# IDC_EXT_Connectors.net
KiCad netlist of a schematic drawn in Altium Designer
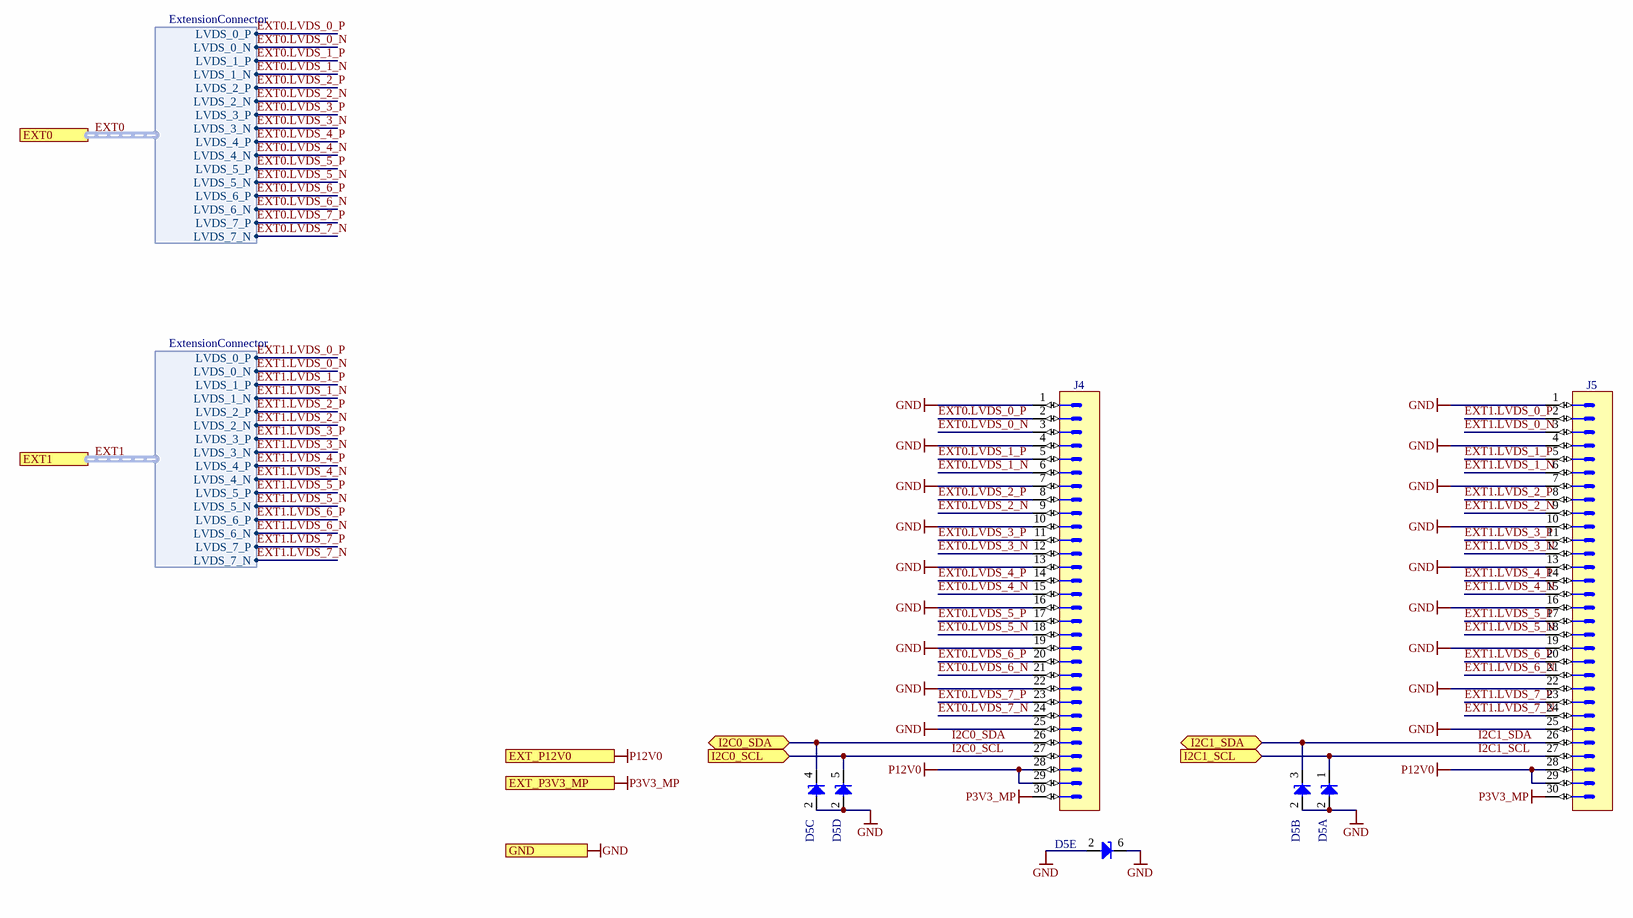
[diagram p0: IDC_EXT_Connectors.SchDoc]

(export (version "E")
  (design (tool "Eeschema 10.0.6"))
  (components
    (comp (ref "D5")
      (value "PESD3V3L5UY")
      (footprint "SOT65P210X110-6N")
      (description "Fivefold ESD Protection Diode Arrays")
      (fields
        (field (name "VOLTAGE") "3.3V")
        (field (name "POWER") "200W")
        (field (name "AUTHOR") "CERN DEM WB")
      )
      (libsource (lib "ICs And Semiconductors") (part "PESD Array 5diodes 6pins Common anode2"))
    )
    (comp (ref "J4")
      (value "~")
      (footprint "3M_N2530-6002RB")
      (description "Connector 30 Male")
      (fields
        (field (name "PART NUMBER") "3M_N2530-6002RB")
        (field (name "MANUFACTURER") "3M")
        (field (name "AUTHOR") "CERN DEM JLC")
      )
      (libsource (lib "Connectors") (part "Connector 30 Male"))
    )
    (comp (ref "J5")
      (value "~")
      (footprint "3M_N2530-6002RB")
      (description "Connector 30 Male")
      (fields
        (field (name "PART NUMBER") "3M_N2530-6002RB")
        (field (name "MANUFACTURER") "3M")
        (field (name "AUTHOR") "CERN DEM JLC")
      )
      (libsource (lib "Connectors") (part "Connector 30 Male"))
    )
  )
  (nets
    (net (code "3") (name "/EXT0.LVDS_0_N") (class "Default")
      (node (ref "J4") (pin "3") (pinfunction "3_3") (pintype "bidirectional"))
    )
    (net (code "4") (name "/EXT0.LVDS_0_P") (class "Default")
      (node (ref "J4") (pin "2") (pinfunction "2_2") (pintype "bidirectional"))
    )
    (net (code "5") (name "/EXT0.LVDS_1_N") (class "Default")
      (node (ref "J4") (pin "6") (pinfunction "6_6") (pintype "bidirectional"))
    )
    (net (code "6") (name "/EXT0.LVDS_1_P") (class "Default")
      (node (ref "J4") (pin "5") (pinfunction "5_5") (pintype "bidirectional"))
    )
    (net (code "7") (name "/EXT0.LVDS_2_N") (class "Default")
      (node (ref "J4") (pin "9") (pinfunction "9_9") (pintype "bidirectional"))
    )
    (net (code "8") (name "/EXT0.LVDS_2_P") (class "Default")
      (node (ref "J4") (pin "8") (pinfunction "8_8") (pintype "bidirectional"))
    )
    (net (code "9") (name "/EXT0.LVDS_3_N") (class "Default")
      (node (ref "J4") (pin "12") (pinfunction "12_12") (pintype "bidirectional"))
    )
    (net (code "10") (name "/EXT0.LVDS_3_P") (class "Default")
      (node (ref "J4") (pin "11") (pinfunction "11_11") (pintype "bidirectional"))
    )
    (net (code "11") (name "/EXT0.LVDS_4_N") (class "Default")
      (node (ref "J4") (pin "15") (pinfunction "15_15") (pintype "bidirectional"))
    )
    (net (code "12") (name "/EXT0.LVDS_4_P") (class "Default")
      (node (ref "J4") (pin "14") (pinfunction "14_14") (pintype "bidirectional"))
    )
    (net (code "13") (name "/EXT0.LVDS_5_N") (class "Default")
      (node (ref "J4") (pin "18") (pinfunction "18_18") (pintype "bidirectional"))
    )
    (net (code "14") (name "/EXT0.LVDS_5_P") (class "Default")
      (node (ref "J4") (pin "17") (pinfunction "17_17") (pintype "bidirectional"))
    )
    (net (code "15") (name "/EXT0.LVDS_6_N") (class "Default")
      (node (ref "J4") (pin "21") (pinfunction "21_21") (pintype "bidirectional"))
    )
    (net (code "16") (name "/EXT0.LVDS_6_P") (class "Default")
      (node (ref "J4") (pin "20") (pinfunction "20_20") (pintype "bidirectional"))
    )
    (net (code "17") (name "/EXT0.LVDS_7_N") (class "Default")
      (node (ref "J4") (pin "24") (pinfunction "24_24") (pintype "bidirectional"))
    )
    (net (code "18") (name "/EXT0.LVDS_7_P") (class "Default")
      (node (ref "J4") (pin "23") (pinfunction "23_23") (pintype "bidirectional"))
    )
    (net (code "20") (name "/EXT1.LVDS_0_N") (class "Default")
      (node (ref "J5") (pin "3") (pinfunction "3_3") (pintype "bidirectional"))
    )
    (net (code "21") (name "/EXT1.LVDS_0_P") (class "Default")
      (node (ref "J5") (pin "2") (pinfunction "2_2") (pintype "bidirectional"))
    )
    (net (code "22") (name "/EXT1.LVDS_1_N") (class "Default")
      (node (ref "J5") (pin "6") (pinfunction "6_6") (pintype "bidirectional"))
    )
    (net (code "23") (name "/EXT1.LVDS_1_P") (class "Default")
      (node (ref "J5") (pin "5") (pinfunction "5_5") (pintype "bidirectional"))
    )
    (net (code "24") (name "/EXT1.LVDS_2_N") (class "Default")
      (node (ref "J5") (pin "9") (pinfunction "9_9") (pintype "bidirectional"))
    )
    (net (code "25") (name "/EXT1.LVDS_2_P") (class "Default")
      (node (ref "J5") (pin "8") (pinfunction "8_8") (pintype "bidirectional"))
    )
    (net (code "26") (name "/EXT1.LVDS_3_N") (class "Default")
      (node (ref "J5") (pin "12") (pinfunction "12_12") (pintype "bidirectional"))
    )
    (net (code "27") (name "/EXT1.LVDS_3_P") (class "Default")
      (node (ref "J5") (pin "11") (pinfunction "11_11") (pintype "bidirectional"))
    )
    (net (code "28") (name "/EXT1.LVDS_4_N") (class "Default")
      (node (ref "J5") (pin "15") (pinfunction "15_15") (pintype "bidirectional"))
    )
    (net (code "29") (name "/EXT1.LVDS_4_P") (class "Default")
      (node (ref "J5") (pin "14") (pinfunction "14_14") (pintype "bidirectional"))
    )
    (net (code "30") (name "/EXT1.LVDS_5_N") (class "Default")
      (node (ref "J5") (pin "18") (pinfunction "18_18") (pintype "bidirectional"))
    )
    (net (code "31") (name "/EXT1.LVDS_5_P") (class "Default")
      (node (ref "J5") (pin "17") (pinfunction "17_17") (pintype "bidirectional"))
    )
    (net (code "32") (name "/EXT1.LVDS_6_N") (class "Default")
      (node (ref "J5") (pin "21") (pinfunction "21_21") (pintype "bidirectional"))
    )
    (net (code "33") (name "/EXT1.LVDS_6_P") (class "Default")
      (node (ref "J5") (pin "20") (pinfunction "20_20") (pintype "bidirectional"))
    )
    (net (code "34") (name "/EXT1.LVDS_7_N") (class "Default")
      (node (ref "J5") (pin "24") (pinfunction "24_24") (pintype "bidirectional"))
    )
    (net (code "35") (name "/EXT1.LVDS_7_P") (class "Default")
      (node (ref "J5") (pin "23") (pinfunction "23_23") (pintype "bidirectional"))
    )
    (net (code "37") (name "/I2C0_SCL") (class "Default")
      (node (ref "D5") (pin "5") (pinfunction "C_5") (pintype "passive"))
      (node (ref "J4") (pin "27") (pinfunction "27_27") (pintype "bidirectional"))
    )
    (net (code "38") (name "/I2C0_SDA") (class "Default")
      (node (ref "D5") (pin "4") (pinfunction "C_4") (pintype "passive"))
      (node (ref "J4") (pin "26") (pinfunction "26_26") (pintype "bidirectional"))
    )
    (net (code "39") (name "/I2C1_SCL") (class "Default")
      (node (ref "D5") (pin "1") (pinfunction "C_1") (pintype "passive"))
      (node (ref "J5") (pin "27") (pinfunction "27_27") (pintype "bidirectional"))
    )
    (net (code "40") (name "/I2C1_SDA") (class "Default")
      (node (ref "D5") (pin "3") (pinfunction "C_3") (pintype "passive"))
      (node (ref "J5") (pin "26") (pinfunction "26_26") (pintype "bidirectional"))
    )
    (net (code "41") (name "GND") (class "Default")
      (node (ref "D5") (pin "2") (pinfunction "A_2") (pintype "passive"))
      (node (ref "D5") (pin "6") (pinfunction "C_6") (pintype "passive"))
      (node (ref "J4") (pin "1") (pinfunction "1_1") (pintype "bidirectional"))
      (node (ref "J4") (pin "10") (pinfunction "10_10") (pintype "bidirectional"))
      (node (ref "J4") (pin "13") (pinfunction "13_13") (pintype "bidirectional"))
      (node (ref "J4") (pin "16") (pinfunction "16_16") (pintype "bidirectional"))
      (node (ref "J4") (pin "19") (pinfunction "19_19") (pintype "bidirectional"))
      (node (ref "J4") (pin "22") (pinfunction "22_22") (pintype "bidirectional"))
      (node (ref "J4") (pin "25") (pinfunction "25_25") (pintype "bidirectional"))
      (node (ref "J4") (pin "4") (pinfunction "4_4") (pintype "bidirectional"))
      (node (ref "J4") (pin "7") (pinfunction "7_7") (pintype "bidirectional"))
      (node (ref "J5") (pin "1") (pinfunction "1_1") (pintype "bidirectional"))
      (node (ref "J5") (pin "10") (pinfunction "10_10") (pintype "bidirectional"))
      (node (ref "J5") (pin "13") (pinfunction "13_13") (pintype "bidirectional"))
      (node (ref "J5") (pin "16") (pinfunction "16_16") (pintype "bidirectional"))
      (node (ref "J5") (pin "19") (pinfunction "19_19") (pintype "bidirectional"))
      (node (ref "J5") (pin "22") (pinfunction "22_22") (pintype "bidirectional"))
      (node (ref "J5") (pin "25") (pinfunction "25_25") (pintype "bidirectional"))
      (node (ref "J5") (pin "4") (pinfunction "4_4") (pintype "bidirectional"))
      (node (ref "J5") (pin "7") (pinfunction "7_7") (pintype "bidirectional"))
    )
    (net (code "42") (name "P3V3_MP") (class "Default")
      (node (ref "J4") (pin "30") (pinfunction "30_30") (pintype "bidirectional"))
      (node (ref "J5") (pin "30") (pinfunction "30_30") (pintype "bidirectional"))
    )
    (net (code "43") (name "P12V0") (class "Default")
      (node (ref "J4") (pin "28") (pinfunction "28_28") (pintype "bidirectional"))
      (node (ref "J4") (pin "29") (pinfunction "29_29") (pintype "bidirectional"))
      (node (ref "J5") (pin "28") (pinfunction "28_28") (pintype "bidirectional"))
      (node (ref "J5") (pin "29") (pinfunction "29_29") (pintype "bidirectional"))
    )
  )
)
